# bender.net
KiCad netlist of a schematic drawn in EAGLE
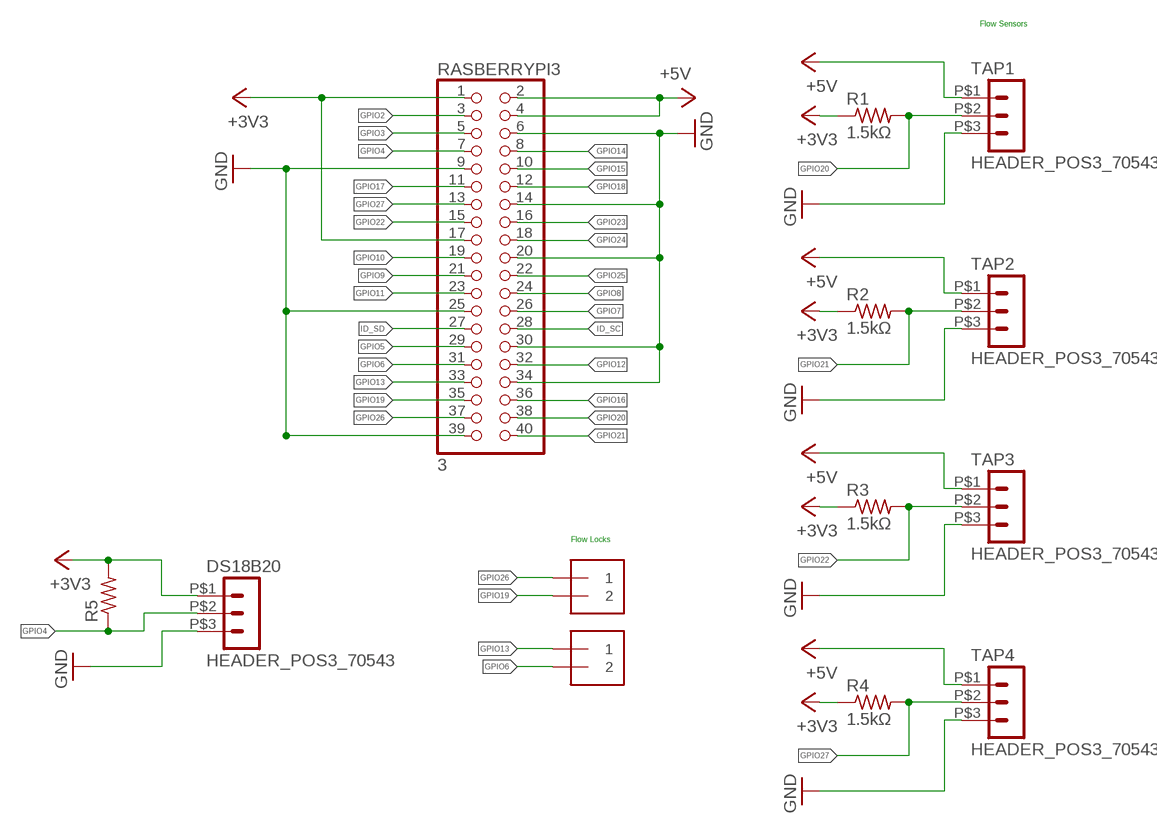
[diagram p0: schematic, sheet 1]

(export (version "E")
  (design (tool "Eeschema 10.0.6"))
  (components
    (comp (ref "DS18B20")
      (value "HEADER_POS3_70543")
      (footprint "eagle-import:70543-POS3")
      (libsource (lib "eagle-import") (part "HEADER_POS3_?70543"))
    )
    (comp (ref "LOCK12")
      (value "1X2-3.5MM")
      (footprint "eagle-import:1X2-3.5MM")
      (libsource (lib "eagle-import") (part "1X2-3.5MM"))
    )
    (comp (ref "LOCK34")
      (value "1X2-3.5MM")
      (footprint "eagle-import:1X2-3.5MM")
      (libsource (lib "eagle-import") (part "1X2-3.5MM"))
    )
    (comp (ref "R1")
      (value "1.5kΩ")
      (footprint "eagle-import:0204_7")
      (libsource (lib "eagle-import") (part "R-US_0204/7"))
    )
    (comp (ref "R2")
      (value "1.5kΩ")
      (footprint "eagle-import:0204_7")
      (libsource (lib "eagle-import") (part "R-US_0204/7"))
    )
    (comp (ref "R3")
      (value "1.5kΩ")
      (footprint "eagle-import:0204_7")
      (libsource (lib "eagle-import") (part "R-US_0204/7"))
    )
    (comp (ref "R4")
      (value "1.5kΩ")
      (footprint "eagle-import:0204_7")
      (libsource (lib "eagle-import") (part "R-US_0204/7"))
    )
    (comp (ref "R5")
      (value "R-US_0204/7")
      (footprint "eagle-import:0204_7")
      (libsource (lib "eagle-import") (part "R-US_0204/7"))
    )
    (comp (ref "RASBERRYPI3")
      (value "3")
      (footprint "eagle-import:2X20")
      (libsource (lib "eagle-import") (part "PINHD-2X20"))
    )
    (comp (ref "TAP1")
      (value "HEADER_POS3_70543")
      (footprint "eagle-import:70543-POS3")
      (libsource (lib "eagle-import") (part "HEADER_POS3_?70543"))
    )
    (comp (ref "TAP2")
      (value "HEADER_POS3_70543")
      (footprint "eagle-import:70543-POS3")
      (libsource (lib "eagle-import") (part "HEADER_POS3_?70543"))
    )
    (comp (ref "TAP3")
      (value "HEADER_POS3_70543")
      (footprint "eagle-import:70543-POS3")
      (libsource (lib "eagle-import") (part "HEADER_POS3_?70543"))
    )
    (comp (ref "TAP4")
      (value "HEADER_POS3_70543")
      (footprint "eagle-import:70543-POS3")
      (libsource (lib "eagle-import") (part "HEADER_POS3_?70543"))
    )
  )
  (nets
    (net (code "1") (name "+3V3") (class "Default")
      (node (ref "DS18B20") (pin "P$1") (pinfunction "1_P$1") (pintype "passive"))
      (node (ref "R1") (pin "1") (pinfunction "1_1") (pintype "passive"))
      (node (ref "R2") (pin "1") (pinfunction "1_1") (pintype "passive"))
      (node (ref "R3") (pin "1") (pinfunction "1_1") (pintype "passive"))
      (node (ref "R4") (pin "1") (pinfunction "1_1") (pintype "passive"))
      (node (ref "R5") (pin "2") (pinfunction "2_2") (pintype "passive"))
      (node (ref "RASBERRYPI3") (pin "1") (pinfunction "3.3V_1") (pintype "passive"))
      (node (ref "RASBERRYPI3") (pin "17") (pinfunction "17_17") (pintype "passive"))
    )
    (net (code "2") (name "+5V") (class "Default")
      (node (ref "RASBERRYPI3") (pin "2") (pinfunction "2_2") (pintype "passive"))
      (node (ref "RASBERRYPI3") (pin "4") (pinfunction "4_4") (pintype "passive"))
      (node (ref "TAP1") (pin "P$1") (pinfunction "1_P$1") (pintype "passive"))
      (node (ref "TAP2") (pin "P$1") (pinfunction "1_P$1") (pintype "passive"))
      (node (ref "TAP3") (pin "P$1") (pinfunction "1_P$1") (pintype "passive"))
      (node (ref "TAP4") (pin "P$1") (pinfunction "1_P$1") (pintype "passive"))
    )
    (net (code "3") (name "GND") (class "Default")
      (node (ref "DS18B20") (pin "P$3") (pinfunction "3_P$3") (pintype "passive"))
      (node (ref "RASBERRYPI3") (pin "14") (pinfunction "14_14") (pintype "passive"))
      (node (ref "RASBERRYPI3") (pin "20") (pinfunction "20_20") (pintype "passive"))
      (node (ref "RASBERRYPI3") (pin "25") (pinfunction "25_25") (pintype "passive"))
      (node (ref "RASBERRYPI3") (pin "30") (pinfunction "30_30") (pintype "passive"))
      (node (ref "RASBERRYPI3") (pin "34") (pinfunction "34_34") (pintype "passive"))
      (node (ref "RASBERRYPI3") (pin "39") (pinfunction "39_39") (pintype "passive"))
      (node (ref "RASBERRYPI3") (pin "6") (pinfunction "6_6") (pintype "passive"))
      (node (ref "RASBERRYPI3") (pin "9") (pinfunction "GND_9") (pintype "passive"))
      (node (ref "TAP1") (pin "P$3") (pinfunction "3_P$3") (pintype "passive"))
      (node (ref "TAP2") (pin "P$3") (pinfunction "3_P$3") (pintype "passive"))
      (node (ref "TAP3") (pin "P$3") (pinfunction "3_P$3") (pintype "passive"))
      (node (ref "TAP4") (pin "P$3") (pinfunction "3_P$3") (pintype "passive"))
    )
    (net (code "4") (name "GPIO2") (class "Default")
      (node (ref "RASBERRYPI3") (pin "3") (pinfunction "GPIO2_3") (pintype "passive"))
    )
    (net (code "5") (name "GPIO3") (class "Default")
      (node (ref "RASBERRYPI3") (pin "5") (pinfunction "GPIO3_5") (pintype "passive"))
    )
    (net (code "6") (name "GPIO4") (class "Default")
      (node (ref "DS18B20") (pin "P$2") (pinfunction "2_P$2") (pintype "passive"))
      (node (ref "R5") (pin "1") (pinfunction "1_1") (pintype "passive"))
      (node (ref "RASBERRYPI3") (pin "7") (pinfunction "GPIO4_7") (pintype "passive"))
    )
    (net (code "7") (name "GPIO5") (class "Default")
      (node (ref "RASBERRYPI3") (pin "29") (pinfunction "29_29") (pintype "passive"))
    )
    (net (code "8") (name "GPIO6") (class "Default")
      (node (ref "LOCK34") (pin "2") (pinfunction "2_2") (pintype "passive"))
      (node (ref "RASBERRYPI3") (pin "31") (pinfunction "31_31") (pintype "passive"))
    )
    (net (code "9") (name "GPIO7") (class "Default")
      (node (ref "RASBERRYPI3") (pin "26") (pinfunction "26_26") (pintype "passive"))
    )
    (net (code "10") (name "GPIO8") (class "Default")
      (node (ref "RASBERRYPI3") (pin "24") (pinfunction "24_24") (pintype "passive"))
    )
    (net (code "11") (name "GPIO9") (class "Default")
      (node (ref "RASBERRYPI3") (pin "21") (pinfunction "21_21") (pintype "passive"))
    )
    (net (code "12") (name "GPIO10") (class "Default")
      (node (ref "RASBERRYPI3") (pin "19") (pinfunction "19_19") (pintype "passive"))
    )
    (net (code "13") (name "GPIO11") (class "Default")
      (node (ref "RASBERRYPI3") (pin "23") (pinfunction "23_23") (pintype "passive"))
    )
    (net (code "14") (name "GPIO12") (class "Default")
      (node (ref "RASBERRYPI3") (pin "32") (pinfunction "32_32") (pintype "passive"))
    )
    (net (code "15") (name "GPIO13") (class "Default")
      (node (ref "LOCK34") (pin "1") (pinfunction "1_1") (pintype "passive"))
      (node (ref "RASBERRYPI3") (pin "33") (pinfunction "33_33") (pintype "passive"))
    )
    (net (code "16") (name "GPIO14") (class "Default")
      (node (ref "RASBERRYPI3") (pin "8") (pinfunction "8_8") (pintype "passive"))
    )
    (net (code "17") (name "GPIO15") (class "Default")
      (node (ref "RASBERRYPI3") (pin "10") (pinfunction "10_10") (pintype "passive"))
    )
    (net (code "18") (name "GPIO16") (class "Default")
      (node (ref "RASBERRYPI3") (pin "36") (pinfunction "36_36") (pintype "passive"))
    )
    (net (code "19") (name "GPIO17") (class "Default")
      (node (ref "RASBERRYPI3") (pin "11") (pinfunction "GPIO17_11") (pintype "passive"))
    )
    (net (code "20") (name "GPIO18") (class "Default")
      (node (ref "RASBERRYPI3") (pin "12") (pinfunction "12_12") (pintype "passive"))
    )
    (net (code "21") (name "GPIO19") (class "Default")
      (node (ref "LOCK12") (pin "2") (pinfunction "2_2") (pintype "passive"))
      (node (ref "RASBERRYPI3") (pin "35") (pinfunction "35_35") (pintype "passive"))
    )
    (net (code "22") (name "GPIO20") (class "Default")
      (node (ref "R1") (pin "2") (pinfunction "2_2") (pintype "passive"))
      (node (ref "RASBERRYPI3") (pin "38") (pinfunction "38_38") (pintype "passive"))
      (node (ref "TAP1") (pin "P$2") (pinfunction "2_P$2") (pintype "passive"))
    )
    (net (code "23") (name "GPIO21") (class "Default")
      (node (ref "R2") (pin "2") (pinfunction "2_2") (pintype "passive"))
      (node (ref "RASBERRYPI3") (pin "40") (pinfunction "40_40") (pintype "passive"))
      (node (ref "TAP2") (pin "P$2") (pinfunction "2_P$2") (pintype "passive"))
    )
    (net (code "24") (name "GPIO22") (class "Default")
      (node (ref "R3") (pin "2") (pinfunction "2_2") (pintype "passive"))
      (node (ref "RASBERRYPI3") (pin "15") (pinfunction "GPIO22_15") (pintype "passive"))
      (node (ref "TAP3") (pin "P$2") (pinfunction "2_P$2") (pintype "passive"))
    )
    (net (code "25") (name "GPIO23") (class "Default")
      (node (ref "RASBERRYPI3") (pin "16") (pinfunction "16_16") (pintype "passive"))
    )
    (net (code "26") (name "GPIO24") (class "Default")
      (node (ref "RASBERRYPI3") (pin "18") (pinfunction "18_18") (pintype "passive"))
    )
    (net (code "27") (name "GPIO25") (class "Default")
      (node (ref "RASBERRYPI3") (pin "22") (pinfunction "22_22") (pintype "passive"))
    )
    (net (code "28") (name "GPIO26") (class "Default")
      (node (ref "LOCK12") (pin "1") (pinfunction "1_1") (pintype "passive"))
      (node (ref "RASBERRYPI3") (pin "37") (pinfunction "37_37") (pintype "passive"))
    )
    (net (code "29") (name "GPIO27") (class "Default")
      (node (ref "R4") (pin "2") (pinfunction "2_2") (pintype "passive"))
      (node (ref "RASBERRYPI3") (pin "13") (pinfunction "GPIO27_13") (pintype "passive"))
      (node (ref "TAP4") (pin "P$2") (pinfunction "2_P$2") (pintype "passive"))
    )
    (net (code "30") (name "ID_SC") (class "Default")
      (node (ref "RASBERRYPI3") (pin "28") (pinfunction "28_28") (pintype "passive"))
    )
    (net (code "31") (name "ID_SD") (class "Default")
      (node (ref "RASBERRYPI3") (pin "27") (pinfunction "27_27") (pintype "passive"))
    )
  )
)
